# voice_board_kombi_smd.net
KiCad netlist of a schematic drawn in EAGLE
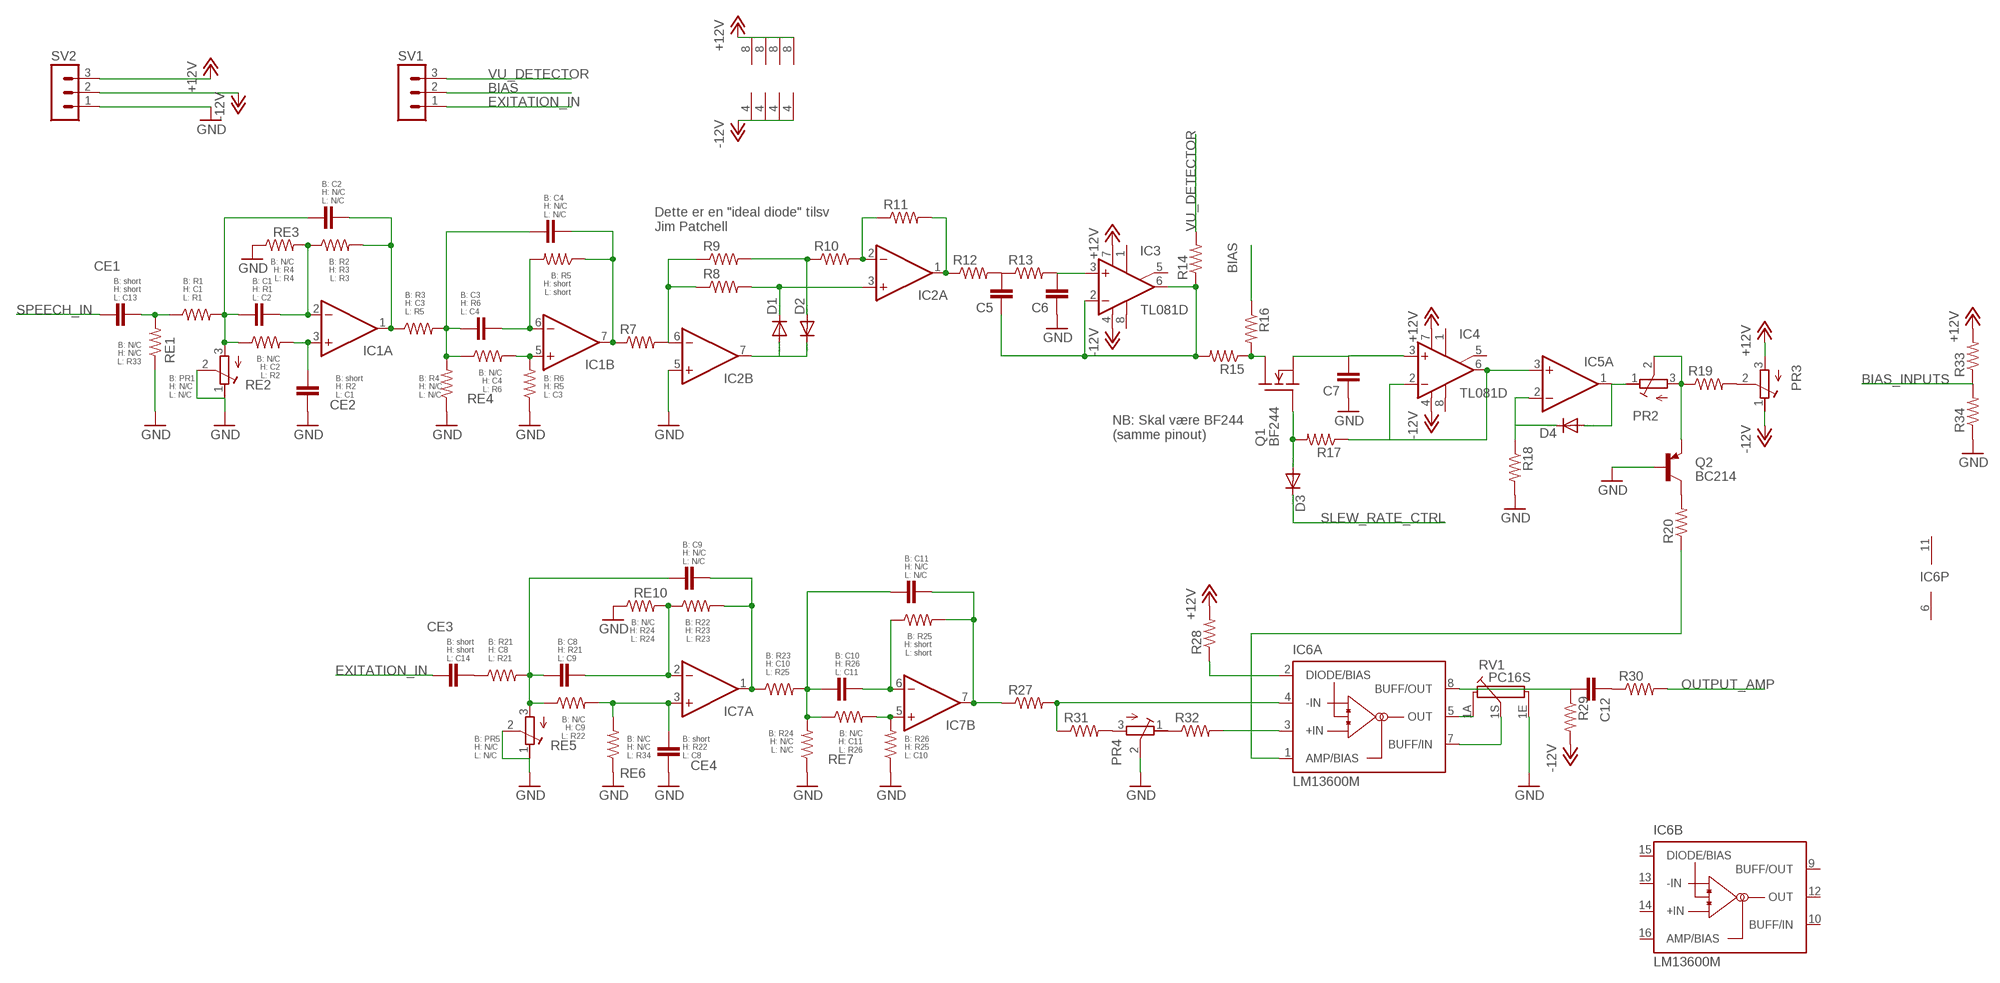
[diagram p0: schematic, sheet 1]

(export (version "E")
  (design (tool "Eeschema 10.0.6"))
  (components
    (comp (ref "C1")
      (value "C-EUC0805")
      (footprint "eagle-import:C0805")
      (libsource (lib "eagle-import") (part "C-EUC0805"))
    )
    (comp (ref "C2")
      (value "C-EUC0805")
      (footprint "eagle-import:C0805")
      (libsource (lib "eagle-import") (part "C-EUC0805"))
    )
    (comp (ref "C3")
      (value "C-EUC0805")
      (footprint "eagle-import:C0805")
      (libsource (lib "eagle-import") (part "C-EUC0805"))
    )
    (comp (ref "C4")
      (value "C-EUC0805")
      (footprint "eagle-import:C0805")
      (libsource (lib "eagle-import") (part "C-EUC0805"))
    )
    (comp (ref "C5")
      (value "C-EUC0805")
      (footprint "eagle-import:C0805")
      (libsource (lib "eagle-import") (part "C-EUC0805"))
    )
    (comp (ref "C6")
      (value "C-EUC0805")
      (footprint "eagle-import:C0805")
      (libsource (lib "eagle-import") (part "C-EUC0805"))
    )
    (comp (ref "C7")
      (value "C-EUC0805")
      (footprint "eagle-import:C0805")
      (libsource (lib "eagle-import") (part "C-EUC0805"))
    )
    (comp (ref "C8")
      (value "C-EUC0805")
      (footprint "eagle-import:C0805")
      (libsource (lib "eagle-import") (part "C-EUC0805"))
    )
    (comp (ref "C9")
      (value "C-EUC0805")
      (footprint "eagle-import:C0805")
      (libsource (lib "eagle-import") (part "C-EUC0805"))
    )
    (comp (ref "C10")
      (value "C-EUC0805")
      (footprint "eagle-import:C0805")
      (libsource (lib "eagle-import") (part "C-EUC0805"))
    )
    (comp (ref "C11")
      (value "C-EUC0805")
      (footprint "eagle-import:C0805")
      (libsource (lib "eagle-import") (part "C-EUC0805"))
    )
    (comp (ref "C12")
      (value "C-EUC0805")
      (footprint "eagle-import:C0805")
      (libsource (lib "eagle-import") (part "C-EUC0805"))
    )
    (comp (ref "CE1")
      (value "C-EUC0805")
      (footprint "eagle-import:C0805")
      (libsource (lib "eagle-import") (part "C-EUC0805"))
    )
    (comp (ref "CE2")
      (value "C-EUC0805")
      (footprint "eagle-import:C0805")
      (libsource (lib "eagle-import") (part "C-EUC0805"))
    )
    (comp (ref "CE3")
      (value "C-EUC0805")
      (footprint "eagle-import:C0805")
      (libsource (lib "eagle-import") (part "C-EUC0805"))
    )
    (comp (ref "CE4")
      (value "C-EUC0805")
      (footprint "eagle-import:C0805")
      (libsource (lib "eagle-import") (part "C-EUC0805"))
    )
    (comp (ref "D1")
      (value "DIODE-SOD80C")
      (footprint "eagle-import:SOD80C")
      (libsource (lib "eagle-import") (part "DIODE-SOD80C"))
    )
    (comp (ref "D2")
      (value "DIODE-SOD80C")
      (footprint "eagle-import:SOD80C")
      (libsource (lib "eagle-import") (part "DIODE-SOD80C"))
    )
    (comp (ref "D3")
      (value "DIODE-SOD80C")
      (footprint "eagle-import:SOD80C")
      (libsource (lib "eagle-import") (part "DIODE-SOD80C"))
    )
    (comp (ref "D4")
      (value "DIODE-SOD80C")
      (footprint "eagle-import:SOD80C")
      (libsource (lib "eagle-import") (part "DIODE-SOD80C"))
    )
    (comp (ref "IC1")
      (value "TL072D")
      (footprint "eagle-import:SO08")
      (libsource (lib "eagle-import") (part "TL072D"))
    )
    (comp (ref "IC2")
      (value "TL072D")
      (footprint "eagle-import:SO08")
      (libsource (lib "eagle-import") (part "TL072D"))
    )
    (comp (ref "IC3")
      (value "TL081D")
      (footprint "eagle-import:SO08")
      (libsource (lib "eagle-import") (part "TL081D"))
    )
    (comp (ref "IC4")
      (value "TL081D")
      (footprint "eagle-import:SO08")
      (libsource (lib "eagle-import") (part "TL081D"))
    )
    (comp (ref "IC5")
      (value "TL072D")
      (footprint "eagle-import:SO08")
      (libsource (lib "eagle-import") (part "TL072D"))
    )
    (comp (ref "IC6")
      (value "LM13600M")
      (footprint "eagle-import:SO16")
      (libsource (lib "eagle-import") (part "LM13600M"))
    )
    (comp (ref "IC7")
      (value "TL072D")
      (footprint "eagle-import:SO08")
      (libsource (lib "eagle-import") (part "TL072D"))
    )
    (comp (ref "PR1")
      (value "R-TRIMMT93XA")
      (footprint "eagle-import:RTRIMT93XA")
      (libsource (lib "eagle-import") (part "R-TRIMMT93XA"))
    )
    (comp (ref "PR2")
      (value "R-TRIMMT93XA")
      (footprint "eagle-import:RTRIMT93XA")
      (libsource (lib "eagle-import") (part "R-TRIMMT93XA"))
    )
    (comp (ref "PR3")
      (value "R-TRIMMT93XA")
      (footprint "eagle-import:RTRIMT93XA")
      (libsource (lib "eagle-import") (part "R-TRIMMT93XA"))
    )
    (comp (ref "PR4")
      (value "R-TRIMMT93XA")
      (footprint "eagle-import:RTRIMT93XA")
      (libsource (lib "eagle-import") (part "R-TRIMMT93XA"))
    )
    (comp (ref "PR5")
      (value "R-TRIMMT93XA")
      (footprint "eagle-import:RTRIMT93XA")
      (libsource (lib "eagle-import") (part "R-TRIMMT93XA"))
    )
    (comp (ref "Q1")
      (value "BF244")
      (footprint "eagle-import:TO-92")
      (libsource (lib "eagle-import") (part "TN0602N3"))
    )
    (comp (ref "Q2")
      (value "BC214")
      (footprint "eagle-import:TO92")
      (libsource (lib "eagle-import") (part "BC214"))
    )
    (comp (ref "R1")
      (value "R-US_R0805")
      (footprint "eagle-import:R0805")
      (libsource (lib "eagle-import") (part "R-US_R0805"))
    )
    (comp (ref "R2")
      (value "R-US_R0805")
      (footprint "eagle-import:R0805")
      (libsource (lib "eagle-import") (part "R-US_R0805"))
    )
    (comp (ref "R3")
      (value "R-US_R0805")
      (footprint "eagle-import:R0805")
      (libsource (lib "eagle-import") (part "R-US_R0805"))
    )
    (comp (ref "R4")
      (value "R-US_R0805")
      (footprint "eagle-import:R0805")
      (libsource (lib "eagle-import") (part "R-US_R0805"))
    )
    (comp (ref "R5")
      (value "R-US_R0805")
      (footprint "eagle-import:R0805")
      (libsource (lib "eagle-import") (part "R-US_R0805"))
    )
    (comp (ref "R6")
      (value "R-US_R0805")
      (footprint "eagle-import:R0805")
      (libsource (lib "eagle-import") (part "R-US_R0805"))
    )
    (comp (ref "R7")
      (value "R-US_R0805")
      (footprint "eagle-import:R0805")
      (libsource (lib "eagle-import") (part "R-US_R0805"))
    )
    (comp (ref "R8")
      (value "R-US_R0805")
      (footprint "eagle-import:R0805")
      (libsource (lib "eagle-import") (part "R-US_R0805"))
    )
    (comp (ref "R9")
      (value "R-US_R0805")
      (footprint "eagle-import:R0805")
      (libsource (lib "eagle-import") (part "R-US_R0805"))
    )
    (comp (ref "R10")
      (value "R-US_R0805")
      (footprint "eagle-import:R0805")
      (libsource (lib "eagle-import") (part "R-US_R0805"))
    )
    (comp (ref "R11")
      (value "R-US_R0805")
      (footprint "eagle-import:R0805")
      (libsource (lib "eagle-import") (part "R-US_R0805"))
    )
    (comp (ref "R12")
      (value "R-US_R0805")
      (footprint "eagle-import:R0805")
      (libsource (lib "eagle-import") (part "R-US_R0805"))
    )
    (comp (ref "R13")
      (value "R-US_R0805")
      (footprint "eagle-import:R0805")
      (libsource (lib "eagle-import") (part "R-US_R0805"))
    )
    (comp (ref "R14")
      (value "R-US_R0805")
      (footprint "eagle-import:R0805")
      (libsource (lib "eagle-import") (part "R-US_R0805"))
    )
    (comp (ref "R15")
      (value "R-US_R0805")
      (footprint "eagle-import:R0805")
      (libsource (lib "eagle-import") (part "R-US_R0805"))
    )
    (comp (ref "R16")
      (value "R-US_R0805")
      (footprint "eagle-import:R0805")
      (libsource (lib "eagle-import") (part "R-US_R0805"))
    )
    (comp (ref "R17")
      (value "R-US_R0805")
      (footprint "eagle-import:R0805")
      (libsource (lib "eagle-import") (part "R-US_R0805"))
    )
    (comp (ref "R18")
      (value "R-US_R0805")
      (footprint "eagle-import:R0805")
      (libsource (lib "eagle-import") (part "R-US_R0805"))
    )
    (comp (ref "R19")
      (value "R-US_R0805")
      (footprint "eagle-import:R0805")
      (libsource (lib "eagle-import") (part "R-US_R0805"))
    )
    (comp (ref "R20")
      (value "R-US_R0805")
      (footprint "eagle-import:R0805")
      (libsource (lib "eagle-import") (part "R-US_R0805"))
    )
    (comp (ref "R21")
      (value "R-US_R0805")
      (footprint "eagle-import:R0805")
      (libsource (lib "eagle-import") (part "R-US_R0805"))
    )
    (comp (ref "R22")
      (value "R-US_R0805")
      (footprint "eagle-import:R0805")
      (libsource (lib "eagle-import") (part "R-US_R0805"))
    )
    (comp (ref "R23")
      (value "R-US_R0805")
      (footprint "eagle-import:R0805")
      (libsource (lib "eagle-import") (part "R-US_R0805"))
    )
    (comp (ref "R24")
      (value "R-US_R0805")
      (footprint "eagle-import:R0805")
      (libsource (lib "eagle-import") (part "R-US_R0805"))
    )
    (comp (ref "R25")
      (value "R-US_R0805")
      (footprint "eagle-import:R0805")
      (libsource (lib "eagle-import") (part "R-US_R0805"))
    )
    (comp (ref "R26")
      (value "R-US_R0805")
      (footprint "eagle-import:R0805")
      (libsource (lib "eagle-import") (part "R-US_R0805"))
    )
    (comp (ref "R27")
      (value "R-US_R0805")
      (footprint "eagle-import:R0805")
      (libsource (lib "eagle-import") (part "R-US_R0805"))
    )
    (comp (ref "R28")
      (value "R-US_R0805")
      (footprint "eagle-import:R0805")
      (libsource (lib "eagle-import") (part "R-US_R0805"))
    )
    (comp (ref "R29")
      (value "R-US_R0805")
      (footprint "eagle-import:R0805")
      (libsource (lib "eagle-import") (part "R-US_R0805"))
    )
    (comp (ref "R30")
      (value "R-US_R0805")
      (footprint "eagle-import:R0805")
      (libsource (lib "eagle-import") (part "R-US_R0805"))
    )
    (comp (ref "R31")
      (value "R-US_R0805")
      (footprint "eagle-import:R0805")
      (libsource (lib "eagle-import") (part "R-US_R0805"))
    )
    (comp (ref "R32")
      (value "R-US_R0805")
      (footprint "eagle-import:R0805")
      (libsource (lib "eagle-import") (part "R-US_R0805"))
    )
    (comp (ref "R33")
      (value "R-US_R0805")
      (footprint "eagle-import:R0805")
      (libsource (lib "eagle-import") (part "R-US_R0805"))
    )
    (comp (ref "R34")
      (value "R-US_R0805")
      (footprint "eagle-import:R0805")
      (libsource (lib "eagle-import") (part "R-US_R0805"))
    )
    (comp (ref "RE1")
      (value "R-US_R0805")
      (footprint "eagle-import:R0805")
      (libsource (lib "eagle-import") (part "R-US_R0805"))
    )
    (comp (ref "RE2")
      (value "R-US_R0805")
      (footprint "eagle-import:R0805")
      (libsource (lib "eagle-import") (part "R-US_R0805"))
    )
    (comp (ref "RE3")
      (value "R-US_R0805")
      (footprint "eagle-import:R0805")
      (libsource (lib "eagle-import") (part "R-US_R0805"))
    )
    (comp (ref "RE4")
      (value "R-US_R0805")
      (footprint "eagle-import:R0805")
      (libsource (lib "eagle-import") (part "R-US_R0805"))
    )
    (comp (ref "RE5")
      (value "R-US_R0805")
      (footprint "eagle-import:R0805")
      (libsource (lib "eagle-import") (part "R-US_R0805"))
    )
    (comp (ref "RE6")
      (value "R-US_R0805")
      (footprint "eagle-import:R0805")
      (libsource (lib "eagle-import") (part "R-US_R0805"))
    )
    (comp (ref "RE7")
      (value "R-US_R0805")
      (footprint "eagle-import:R0805")
      (libsource (lib "eagle-import") (part "R-US_R0805"))
    )
    (comp (ref "RE10")
      (value "R-US_R0805")
      (footprint "eagle-import:R0805")
      (libsource (lib "eagle-import") (part "R-US_R0805"))
    )
    (comp (ref "RV1")
      (value "PC16S")
      (footprint "eagle-import:PC16S")
      (libsource (lib "eagle-import") (part "PC16S"))
    )
    (comp (ref "SV1")
      (value "MA03-1")
      (footprint "eagle-import:MA03-1")
      (libsource (lib "eagle-import") (part "MA03-1"))
    )
    (comp (ref "SV2")
      (value "MA03-1")
      (footprint "eagle-import:MA03-1")
      (libsource (lib "eagle-import") (part "MA03-1"))
    )
  )
  (nets
    (net (code "1") (name "+12V") (class "Default")
      (node (ref "IC1") (pin "8") (pinfunction "V+_8") (pintype "power_in"))
      (node (ref "IC2") (pin "8") (pinfunction "V+_8") (pintype "power_in"))
      (node (ref "IC3") (pin "7") (pinfunction "V+_7") (pintype "power_in"))
      (node (ref "IC4") (pin "7") (pinfunction "V+_7") (pintype "power_in"))
      (node (ref "IC5") (pin "8") (pinfunction "V+_8") (pintype "power_in"))
      (node (ref "IC7") (pin "8") (pinfunction "V+_8") (pintype "power_in"))
      (node (ref "PR3") (pin "3") (pinfunction "A_3") (pintype "passive"))
      (node (ref "R28") (pin "2") (pinfunction "2_2") (pintype "passive"))
      (node (ref "R33") (pin "2") (pinfunction "2_2") (pintype "passive"))
      (node (ref "SV2") (pin "3") (pinfunction "3_3") (pintype "passive"))
    )
    (net (code "2") (name "-12V") (class "Default")
      (node (ref "IC1") (pin "4") (pinfunction "V-_4") (pintype "power_in"))
      (node (ref "IC2") (pin "4") (pinfunction "V-_4") (pintype "power_in"))
      (node (ref "IC3") (pin "4") (pinfunction "V-_4") (pintype "power_in"))
      (node (ref "IC4") (pin "4") (pinfunction "V-_4") (pintype "power_in"))
      (node (ref "IC5") (pin "4") (pinfunction "V-_4") (pintype "power_in"))
      (node (ref "IC7") (pin "4") (pinfunction "V-_4") (pintype "power_in"))
      (node (ref "PR3") (pin "1") (pinfunction "E_1") (pintype "passive"))
      (node (ref "R29") (pin "2") (pinfunction "2_2") (pintype "passive"))
      (node (ref "SV2") (pin "2") (pinfunction "2_2") (pintype "passive"))
    )
    (net (code "3") (name "/BIAS") (class "Default")
      (node (ref "R16") (pin "1") (pinfunction "1_1") (pintype "passive"))
      (node (ref "SV1") (pin "2") (pinfunction "2_2") (pintype "passive"))
    )
    (net (code "4") (name "/BIAS_INPUTS") (class "Default")
      (node (ref "R33") (pin "1") (pinfunction "1_1") (pintype "passive"))
      (node (ref "R34") (pin "2") (pinfunction "2_2") (pintype "passive"))
    )
    (net (code "5") (name "/EXITATION_IN") (class "Default")
      (node (ref "CE3") (pin "1") (pinfunction "1_1") (pintype "passive"))
      (node (ref "SV1") (pin "1") (pinfunction "1_1") (pintype "passive"))
    )
    (net (code "6") (name "/OUTPUT_AMP") (class "Default")
      (node (ref "R30") (pin "2") (pinfunction "2_2") (pintype "passive"))
    )
    (net (code "7") (name "/SLEW_RATE_CTRL") (class "Default")
      (node (ref "D3") (pin "C") (pinfunction "C_C") (pintype "passive"))
    )
    (net (code "8") (name "/SPEECH_IN") (class "Default")
      (node (ref "CE1") (pin "1") (pinfunction "1_1") (pintype "passive"))
    )
    (net (code "9") (name "/V+") (class "Default")
      (node (ref "IC6") (pin "11") (pinfunction "V+_11") (pintype "power_in"))
    )
    (net (code "10") (name "/V-") (class "Default")
      (node (ref "IC6") (pin "6") (pinfunction "V-_6") (pintype "power_in"))
    )
    (net (code "11") (name "/VU_DETECTOR") (class "Default")
      (node (ref "R14") (pin "2") (pinfunction "2_2") (pintype "passive"))
      (node (ref "SV1") (pin "3") (pinfunction "3_3") (pintype "passive"))
    )
    (net (code "12") (name "GND") (class "Default")
      (node (ref "C6") (pin "1") (pinfunction "1_1") (pintype "passive"))
      (node (ref "C7") (pin "1") (pinfunction "1_1") (pintype "passive"))
      (node (ref "CE2") (pin "1") (pinfunction "1_1") (pintype "passive"))
      (node (ref "CE4") (pin "1") (pinfunction "1_1") (pintype "passive"))
      (node (ref "IC2") (pin "5") (pinfunction "+IN_5") (pintype "input"))
      (node (ref "PR1") (pin "1") (pinfunction "E_1") (pintype "passive"))
      (node (ref "PR1") (pin "2") (pinfunction "S_2") (pintype "passive"))
      (node (ref "PR4") (pin "2") (pinfunction "S_2") (pintype "passive"))
      (node (ref "PR5") (pin "1") (pinfunction "E_1") (pintype "passive"))
      (node (ref "PR5") (pin "2") (pinfunction "S_2") (pintype "passive"))
      (node (ref "Q2") (pin "2") (pinfunction "B_2") (pintype "passive"))
      (node (ref "R18") (pin "2") (pinfunction "2_2") (pintype "passive"))
      (node (ref "R24") (pin "1") (pinfunction "1_1") (pintype "passive"))
      (node (ref "R26") (pin "1") (pinfunction "1_1") (pintype "passive"))
      (node (ref "R34") (pin "1") (pinfunction "1_1") (pintype "passive"))
      (node (ref "R4") (pin "1") (pinfunction "1_1") (pintype "passive"))
      (node (ref "R6") (pin "1") (pinfunction "1_1") (pintype "passive"))
      (node (ref "RE1") (pin "1") (pinfunction "1_1") (pintype "passive"))
      (node (ref "RE10") (pin "1") (pinfunction "1_1") (pintype "passive"))
      (node (ref "RE3") (pin "1") (pinfunction "1_1") (pintype "passive"))
      (node (ref "RE6") (pin "1") (pinfunction "1_1") (pintype "passive"))
      (node (ref "RV1") (pin "1E") (pinfunction "1E_1E") (pintype "passive"))
      (node (ref "SV2") (pin "1") (pinfunction "1_1") (pintype "passive"))
    )
    (net (code "13") (name "Net-(C3-Pad1)") (class "Default")
      (node (ref "C3") (pin "1") (pinfunction "1_1") (pintype "passive"))
      (node (ref "C4") (pin "1") (pinfunction "1_1") (pintype "passive"))
      (node (ref "R3") (pin "2") (pinfunction "2_2") (pintype "passive"))
      (node (ref "R4") (pin "2") (pinfunction "2_2") (pintype "passive"))
      (node (ref "RE4") (pin "1") (pinfunction "1_1") (pintype "passive"))
    )
    (net (code "14") (name "Net-(C5-Pad2)") (class "Default")
      (node (ref "C5") (pin "2") (pinfunction "2_2") (pintype "passive"))
      (node (ref "R12") (pin "2") (pinfunction "2_2") (pintype "passive"))
      (node (ref "R13") (pin "1") (pinfunction "1_1") (pintype "passive"))
    )
    (net (code "15") (name "Net-(C10-Pad2)") (class "Default")
      (node (ref "C10") (pin "2") (pinfunction "2_2") (pintype "passive"))
      (node (ref "C11") (pin "2") (pinfunction "2_2") (pintype "passive"))
      (node (ref "R23") (pin "2") (pinfunction "2_2") (pintype "passive"))
      (node (ref "R24") (pin "2") (pinfunction "2_2") (pintype "passive"))
      (node (ref "RE7") (pin "1") (pinfunction "1_1") (pintype "passive"))
    )
    (net (code "16") (name "Net-(C12-Pad1)") (class "Default")
      (node (ref "C12") (pin "1") (pinfunction "1_1") (pintype "passive"))
      (node (ref "R30") (pin "1") (pinfunction "1_1") (pintype "passive"))
    )
    (net (code "17") (name "Net-(CE1-Pad2)") (class "Default")
      (node (ref "CE1") (pin "2") (pinfunction "2_2") (pintype "passive"))
      (node (ref "R1") (pin "1") (pinfunction "1_1") (pintype "passive"))
      (node (ref "RE1") (pin "2") (pinfunction "2_2") (pintype "passive"))
    )
    (net (code "18") (name "Net-(CE3-Pad2)") (class "Default")
      (node (ref "CE3") (pin "2") (pinfunction "2_2") (pintype "passive"))
      (node (ref "R21") (pin "1") (pinfunction "1_1") (pintype "passive"))
    )
    (net (code "19") (name "Net-(D2-PadA)") (class "Default")
      (node (ref "D2") (pin "A") (pinfunction "A_A") (pintype "passive"))
      (node (ref "R10") (pin "1") (pinfunction "1_1") (pintype "passive"))
      (node (ref "R9") (pin "2") (pinfunction "2_2") (pintype "passive"))
    )
    (net (code "20") (name "Net-(IC1A-+IN)") (class "Default")
      (node (ref "CE2") (pin "2") (pinfunction "2_2") (pintype "passive"))
      (node (ref "IC1") (pin "3") (pinfunction "+IN_3") (pintype "input"))
      (node (ref "RE2") (pin "2") (pinfunction "2_2") (pintype "passive"))
    )
    (net (code "21") (name "Net-(IC1A--IN)") (class "Default")
      (node (ref "C1") (pin "2") (pinfunction "2_2") (pintype "passive"))
      (node (ref "IC1") (pin "2") (pinfunction "-IN_2") (pintype "input"))
      (node (ref "R2") (pin "1") (pinfunction "1_1") (pintype "passive"))
      (node (ref "RE3") (pin "2") (pinfunction "2_2") (pintype "passive"))
    )
    (net (code "22") (name "Net-(IC1A-OUT)") (class "Default")
      (node (ref "C2") (pin "2") (pinfunction "2_2") (pintype "passive"))
      (node (ref "IC1") (pin "1") (pinfunction "OUT_1") (pintype "output"))
      (node (ref "R2") (pin "2") (pinfunction "2_2") (pintype "passive"))
      (node (ref "R3") (pin "1") (pinfunction "1_1") (pintype "passive"))
    )
    (net (code "23") (name "Net-(IC1B-+IN)") (class "Default")
      (node (ref "IC1") (pin "5") (pinfunction "+IN_5") (pintype "input"))
      (node (ref "R6") (pin "2") (pinfunction "2_2") (pintype "passive"))
      (node (ref "RE4") (pin "2") (pinfunction "2_2") (pintype "passive"))
    )
    (net (code "24") (name "Net-(IC1B--IN)") (class "Default")
      (node (ref "C3") (pin "2") (pinfunction "2_2") (pintype "passive"))
      (node (ref "IC1") (pin "6") (pinfunction "-IN_6") (pintype "input"))
      (node (ref "R5") (pin "2") (pinfunction "2_2") (pintype "passive"))
    )
    (net (code "25") (name "Net-(IC1B-OUT)") (class "Default")
      (node (ref "C4") (pin "2") (pinfunction "2_2") (pintype "passive"))
      (node (ref "IC1") (pin "7") (pinfunction "OUT_7") (pintype "output"))
      (node (ref "R5") (pin "1") (pinfunction "1_1") (pintype "passive"))
      (node (ref "R7") (pin "1") (pinfunction "1_1") (pintype "passive"))
    )
    (net (code "26") (name "Net-(IC2A-+IN)") (class "Default")
      (node (ref "D1") (pin "C") (pinfunction "C_C") (pintype "passive"))
      (node (ref "IC2") (pin "3") (pinfunction "+IN_3") (pintype "input"))
      (node (ref "R8") (pin "2") (pinfunction "2_2") (pintype "passive"))
    )
    (net (code "27") (name "Net-(IC2A--IN)") (class "Default")
      (node (ref "IC2") (pin "2") (pinfunction "-IN_2") (pintype "input"))
      (node (ref "R10") (pin "2") (pinfunction "2_2") (pintype "passive"))
      (node (ref "R11") (pin "1") (pinfunction "1_1") (pintype "passive"))
    )
    (net (code "28") (name "Net-(IC2A-OUT)") (class "Default")
      (node (ref "IC2") (pin "1") (pinfunction "OUT_1") (pintype "output"))
      (node (ref "R11") (pin "2") (pinfunction "2_2") (pintype "passive"))
      (node (ref "R12") (pin "1") (pinfunction "1_1") (pintype "passive"))
    )
    (net (code "29") (name "Net-(IC2B--IN)") (class "Default")
      (node (ref "IC2") (pin "6") (pinfunction "-IN_6") (pintype "input"))
      (node (ref "R7") (pin "2") (pinfunction "2_2") (pintype "passive"))
      (node (ref "R8") (pin "1") (pinfunction "1_1") (pintype "passive"))
      (node (ref "R9") (pin "1") (pinfunction "1_1") (pintype "passive"))
    )
    (net (code "30") (name "Net-(IC2B-OUT)") (class "Default")
      (node (ref "D1") (pin "A") (pinfunction "A_A") (pintype "passive"))
      (node (ref "D2") (pin "C") (pinfunction "C_C") (pintype "passive"))
      (node (ref "IC2") (pin "7") (pinfunction "OUT_7") (pintype "output"))
    )
    (net (code "31") (name "Net-(IC3-+IN)") (class "Default")
      (node (ref "C6") (pin "2") (pinfunction "2_2") (pintype "passive"))
      (node (ref "IC3") (pin "3") (pinfunction "+IN_3") (pintype "input"))
      (node (ref "R13") (pin "2") (pinfunction "2_2") (pintype "passive"))
    )
    (net (code "32") (name "Net-(IC3--IN)") (class "Default")
      (node (ref "C5") (pin "1") (pinfunction "1_1") (pintype "passive"))
      (node (ref "IC3") (pin "2") (pinfunction "-IN_2") (pintype "input"))
      (node (ref "IC3") (pin "6") (pinfunction "OUT_6") (pintype "output"))
      (node (ref "R14") (pin "1") (pinfunction "1_1") (pintype "passive"))
      (node (ref "R15") (pin "2") (pinfunction "2_2") (pintype "passive"))
    )
    (net (code "33") (name "Net-(IC4-+IN)") (class "Default")
      (node (ref "C7") (pin "2") (pinfunction "2_2") (pintype "passive"))
      (node (ref "IC4") (pin "3") (pinfunction "+IN_3") (pintype "input"))
      (node (ref "Q1") (pin "1") (pinfunction "S_1") (pintype "passive"))
    )
    (net (code "34") (name "Net-(IC4--IN)") (class "Default")
      (node (ref "IC4") (pin "2") (pinfunction "-IN_2") (pintype "input"))
      (node (ref "IC4") (pin "6") (pinfunction "OUT_6") (pintype "output"))
      (node (ref "IC5") (pin "3") (pinfunction "+IN_3") (pintype "input"))
      (node (ref "R17") (pin "1") (pinfunction "1_1") (pintype "passive"))
    )
    (net (code "35") (name "Net-(IC5A--IN)") (class "Default")
      (node (ref "D4") (pin "C") (pinfunction "C_C") (pintype "passive"))
      (node (ref "IC5") (pin "2") (pinfunction "-IN_2") (pintype "input"))
      (node (ref "R18") (pin "1") (pinfunction "1_1") (pintype "passive"))
    )
    (net (code "36") (name "Net-(IC5A-OUT)") (class "Default")
      (node (ref "D4") (pin "A") (pinfunction "A_A") (pintype "passive"))
      (node (ref "IC5") (pin "1") (pinfunction "OUT_1") (pintype "output"))
      (node (ref "PR2") (pin "1") (pinfunction "E_1") (pintype "passive"))
    )
    (net (code "37") (name "Net-(IC6A-+IN)") (class "Default")
      (node (ref "IC6") (pin "3") (pinfunction "+IN_3") (pintype "input"))
      (node (ref "R32") (pin "2") (pinfunction "2_2") (pintype "passive"))
    )
    (net (code "38") (name "Net-(IC6A--IN)") (class "Default")
      (node (ref "IC6") (pin "4") (pinfunction "-IN_4") (pintype "input"))
      (node (ref "R27") (pin "2") (pinfunction "2_2") (pintype "passive"))
      (node (ref "R31") (pin "1") (pinfunction "1_1") (pintype "passive"))
    )
    (net (code "39") (name "Net-(IC6A-AMP{slash}BIAS)") (class "Default")
      (node (ref "IC6") (pin "1") (pinfunction "AMP/BIAS_1") (pintype "passive"))
      (node (ref "R20") (pin "1") (pinfunction "1_1") (pintype "passive"))
    )
    (net (code "40") (name "Net-(IC6A-BUFF{slash}IN)") (class "Default")
      (node (ref "IC6") (pin "7") (pinfunction "BUFF/IN_7") (pintype "input"))
      (node (ref "RV1") (pin "1S") (pinfunction "1S_1S") (pintype "passive"))
    )
    (net (code "41") (name "Net-(IC6A-BUFF{slash}OUT)") (class "Default")
      (node (ref "C12") (pin "2") (pinfunction "2_2") (pintype "passive"))
      (node (ref "IC6") (pin "8") (pinfunction "BUFF/OUT_8") (pintype "output"))
      (node (ref "R29") (pin "1") (pinfunction "1_1") (pintype "passive"))
    )
    (net (code "42") (name "Net-(IC6A-DIODE{slash}BIAS)") (class "Default")
      (node (ref "IC6") (pin "2") (pinfunction "DIODE/BIAS_2") (pintype "passive"))
      (node (ref "R28") (pin "1") (pinfunction "1_1") (pintype "passive"))
    )
    (net (code "43") (name "Net-(IC6A-OUT)") (class "Default")
      (node (ref "IC6") (pin "5") (pinfunction "OUT_5") (pintype "output"))
      (node (ref "RV1") (pin "1A") (pinfunction "1A_1A") (pintype "passive"))
    )
    (net (code "44") (name "Net-(IC7A-+IN)") (class "Default")
      (node (ref "CE4") (pin "2") (pinfunction "2_2") (pintype "passive"))
      (node (ref "IC7") (pin "3") (pinfunction "+IN_3") (pintype "input"))
      (node (ref "RE5") (pin "2") (pinfunction "2_2") (pintype "passive"))
      (node (ref "RE6") (pin "2") (pinfunction "2_2") (pintype "passive"))
    )
    (net (code "45") (name "Net-(IC7A--IN)") (class "Default")
      (node (ref "C8") (pin "1") (pinfunction "1_1") (pintype "passive"))
      (node (ref "IC7") (pin "2") (pinfunction "-IN_2") (pintype "input"))
      (node (ref "R22") (pin "1") (pinfunction "1_1") (pintype "passive"))
      (node (ref "RE10") (pin "2") (pinfunction "2_2") (pintype "passive"))
    )
    (net (code "46") (name "Net-(IC7A-OUT)") (class "Default")
      (node (ref "C9") (pin "1") (pinfunction "1_1") (pintype "passive"))
      (node (ref "IC7") (pin "1") (pinfunction "OUT_1") (pintype "output"))
      (node (ref "R22") (pin "2") (pinfunction "2_2") (pintype "passive"))
      (node (ref "R23") (pin "1") (pinfunction "1_1") (pintype "passive"))
    )
    (net (code "47") (name "Net-(IC7B-+IN)") (class "Default")
      (node (ref "IC7") (pin "5") (pinfunction "+IN_5") (pintype "input"))
      (node (ref "R26") (pin "2") (pinfunction "2_2") (pintype "passive"))
      (node (ref "RE7") (pin "2") (pinfunction "2_2") (pintype "passive"))
    )
    (net (code "48") (name "Net-(IC7B--IN)") (class "Default")
      (node (ref "C10") (pin "1") (pinfunction "1_1") (pintype "passive"))
      (node (ref "IC7") (pin "6") (pinfunction "-IN_6") (pintype "input"))
      (node (ref "R25") (pin "1") (pinfunction "1_1") (pintype "passive"))
    )
    (net (code "49") (name "Net-(IC7B-OUT)") (class "Default")
      (node (ref "C11") (pin "1") (pinfunction "1_1") (pintype "passive"))
      (node (ref "IC7") (pin "7") (pinfunction "OUT_7") (pintype "output"))
      (node (ref "R25") (pin "2") (pinfunction "2_2") (pintype "passive"))
      (node (ref "R27") (pin "1") (pinfunction "1_1") (pintype "passive"))
    )
    (net (code "50") (name "Net-(PR1-A)") (class "Default")
      (node (ref "C1") (pin "1") (pinfunction "1_1") (pintype "passive"))
      (node (ref "C2") (pin "1") (pinfunction "1_1") (pintype "passive"))
      (node (ref "PR1") (pin "3") (pinfunction "A_3") (pintype "passive"))
      (node (ref "R1") (pin "2") (pinfunction "2_2") (pintype "passive"))
      (node (ref "RE2") (pin "1") (pinfunction "1_1") (pintype "passive"))
    )
    (net (code "51") (name "Net-(PR2-A)") (class "Default")
      (node (ref "PR2") (pin "2") (pinfunction "S_2") (pintype "passive"))
      (node (ref "PR2") (pin "3") (pinfunction "A_3") (pintype "passive"))
      (node (ref "Q2") (pin "1") (pinfunction "E_1") (pintype "passive"))
      (node (ref "R19") (pin "1") (pinfunction "1_1") (pintype "passive"))
    )
    (net (code "52") (name "Net-(PR3-S)") (class "Default")
      (node (ref "PR3") (pin "2") (pinfunction "S_2") (pintype "passive"))
      (node (ref "R19") (pin "2") (pinfunction "2_2") (pintype "passive"))
    )
    (net (code "53") (name "Net-(PR4-A)") (class "Default")
      (node (ref "PR4") (pin "3") (pinfunction "A_3") (pintype "passive"))
      (node (ref "R31") (pin "2") (pinfunction "2_2") (pintype "passive"))
    )
    (net (code "54") (name "Net-(PR4-E)") (class "Default")
      (node (ref "PR4") (pin "1") (pinfunction "E_1") (pintype "passive"))
      (node (ref "R32") (pin "1") (pinfunction "1_1") (pintype "passive"))
    )
    (net (code "55") (name "Net-(PR5-A)") (class "Default")
      (node (ref "C8") (pin "2") (pinfunction "2_2") (pintype "passive"))
      (node (ref "C9") (pin "2") (pinfunction "2_2") (pintype "passive"))
      (node (ref "PR5") (pin "3") (pinfunction "A_3") (pintype "passive"))
      (node (ref "R21") (pin "2") (pinfunction "2_2") (pintype "passive"))
      (node (ref "RE5") (pin "1") (pinfunction "1_1") (pintype "passive"))
    )
    (net (code "56") (name "Net-(Q1-D)") (class "Default")
      (node (ref "Q1") (pin "3") (pinfunction "D_3") (pintype "passive"))
      (node (ref "R15") (pin "1") (pinfunction "1_1") (pintype "passive"))
      (node (ref "R16") (pin "2") (pinfunction "2_2") (pintype "passive"))
    )
    (net (code "57") (name "Net-(Q1-G)") (class "Default")
      (node (ref "D3") (pin "A") (pinfunction "A_A") (pintype "passive"))
      (node (ref "Q1") (pin "2") (pinfunction "G_2") (pintype "passive"))
      (node (ref "R17") (pin "2") (pinfunction "2_2") (pintype "passive"))
    )
    (net (code "58") (name "Net-(Q2-C)") (class "Default")
      (node (ref "Q2") (pin "3") (pinfunction "C_3") (pintype "passive"))
      (node (ref "R20") (pin "2") (pinfunction "2_2") (pintype "passive"))
    )
    (net (code "59") (name "unconnected-(IC3-ON1-Pad1)") (class "Default")
      (node (ref "IC3") (pin "1") (pinfunction "ON1_1") (pintype "passive"))
    )
    (net (code "60") (name "unconnected-(IC3-ON2-Pad5)") (class "Default")
      (node (ref "IC3") (pin "5") (pinfunction "ON2_5") (pintype "passive"))
    )
    (net (code "61") (name "unconnected-(IC3-OPT-Pad8)") (class "Default")
      (node (ref "IC3") (pin "8") (pinfunction "OPT_8") (pintype "passive"))
    )
    (net (code "62") (name "unconnected-(IC4-ON1-Pad1)") (class "Default")
      (node (ref "IC4") (pin "1") (pinfunction "ON1_1") (pintype "passive"))
    )
    (net (code "63") (name "unconnected-(IC4-ON2-Pad5)") (class "Default")
      (node (ref "IC4") (pin "5") (pinfunction "ON2_5") (pintype "passive"))
    )
    (net (code "64") (name "unconnected-(IC4-OPT-Pad8)") (class "Default")
      (node (ref "IC4") (pin "8") (pinfunction "OPT_8") (pintype "passive"))
    )
    (net (code "65") (name "unconnected-(IC6B-+IN-Pad14)") (class "Default")
      (node (ref "IC6") (pin "14") (pinfunction "+IN_14") (pintype "input"))
    )
    (net (code "66") (name "unconnected-(IC6B--IN-Pad13)") (class "Default")
      (node (ref "IC6") (pin "13") (pinfunction "-IN_13") (pintype "input"))
    )
    (net (code "67") (name "unconnected-(IC6B-AMP{slash}BIAS-Pad16)") (class "Default")
      (node (ref "IC6") (pin "16") (pinfunction "AMP/BIAS_16") (pintype "passive"))
    )
    (net (code "68") (name "unconnected-(IC6B-BUFF{slash}IN-Pad10)") (class "Default")
      (node (ref "IC6") (pin "10") (pinfunction "BUFF/IN_10") (pintype "input"))
    )
    (net (code "69") (name "unconnected-(IC6B-BUFF{slash}OUT-Pad9)") (class "Default")
      (node (ref "IC6") (pin "9") (pinfunction "BUFF/OUT_9") (pintype "output"))
    )
    (net (code "70") (name "unconnected-(IC6B-DIODE{slash}BIAS-Pad15)") (class "Default")
      (node (ref "IC6") (pin "15") (pinfunction "DIODE/BIAS_15") (pintype "passive"))
    )
    (net (code "71") (name "unconnected-(IC6B-OUT-Pad12)") (class "Default")
      (node (ref "IC6") (pin "12") (pinfunction "OUT_12") (pintype "output"))
    )
  )
)
